# steering_wheel_V3_1.net
KiCad netlist of a schematic drawn in EAGLE
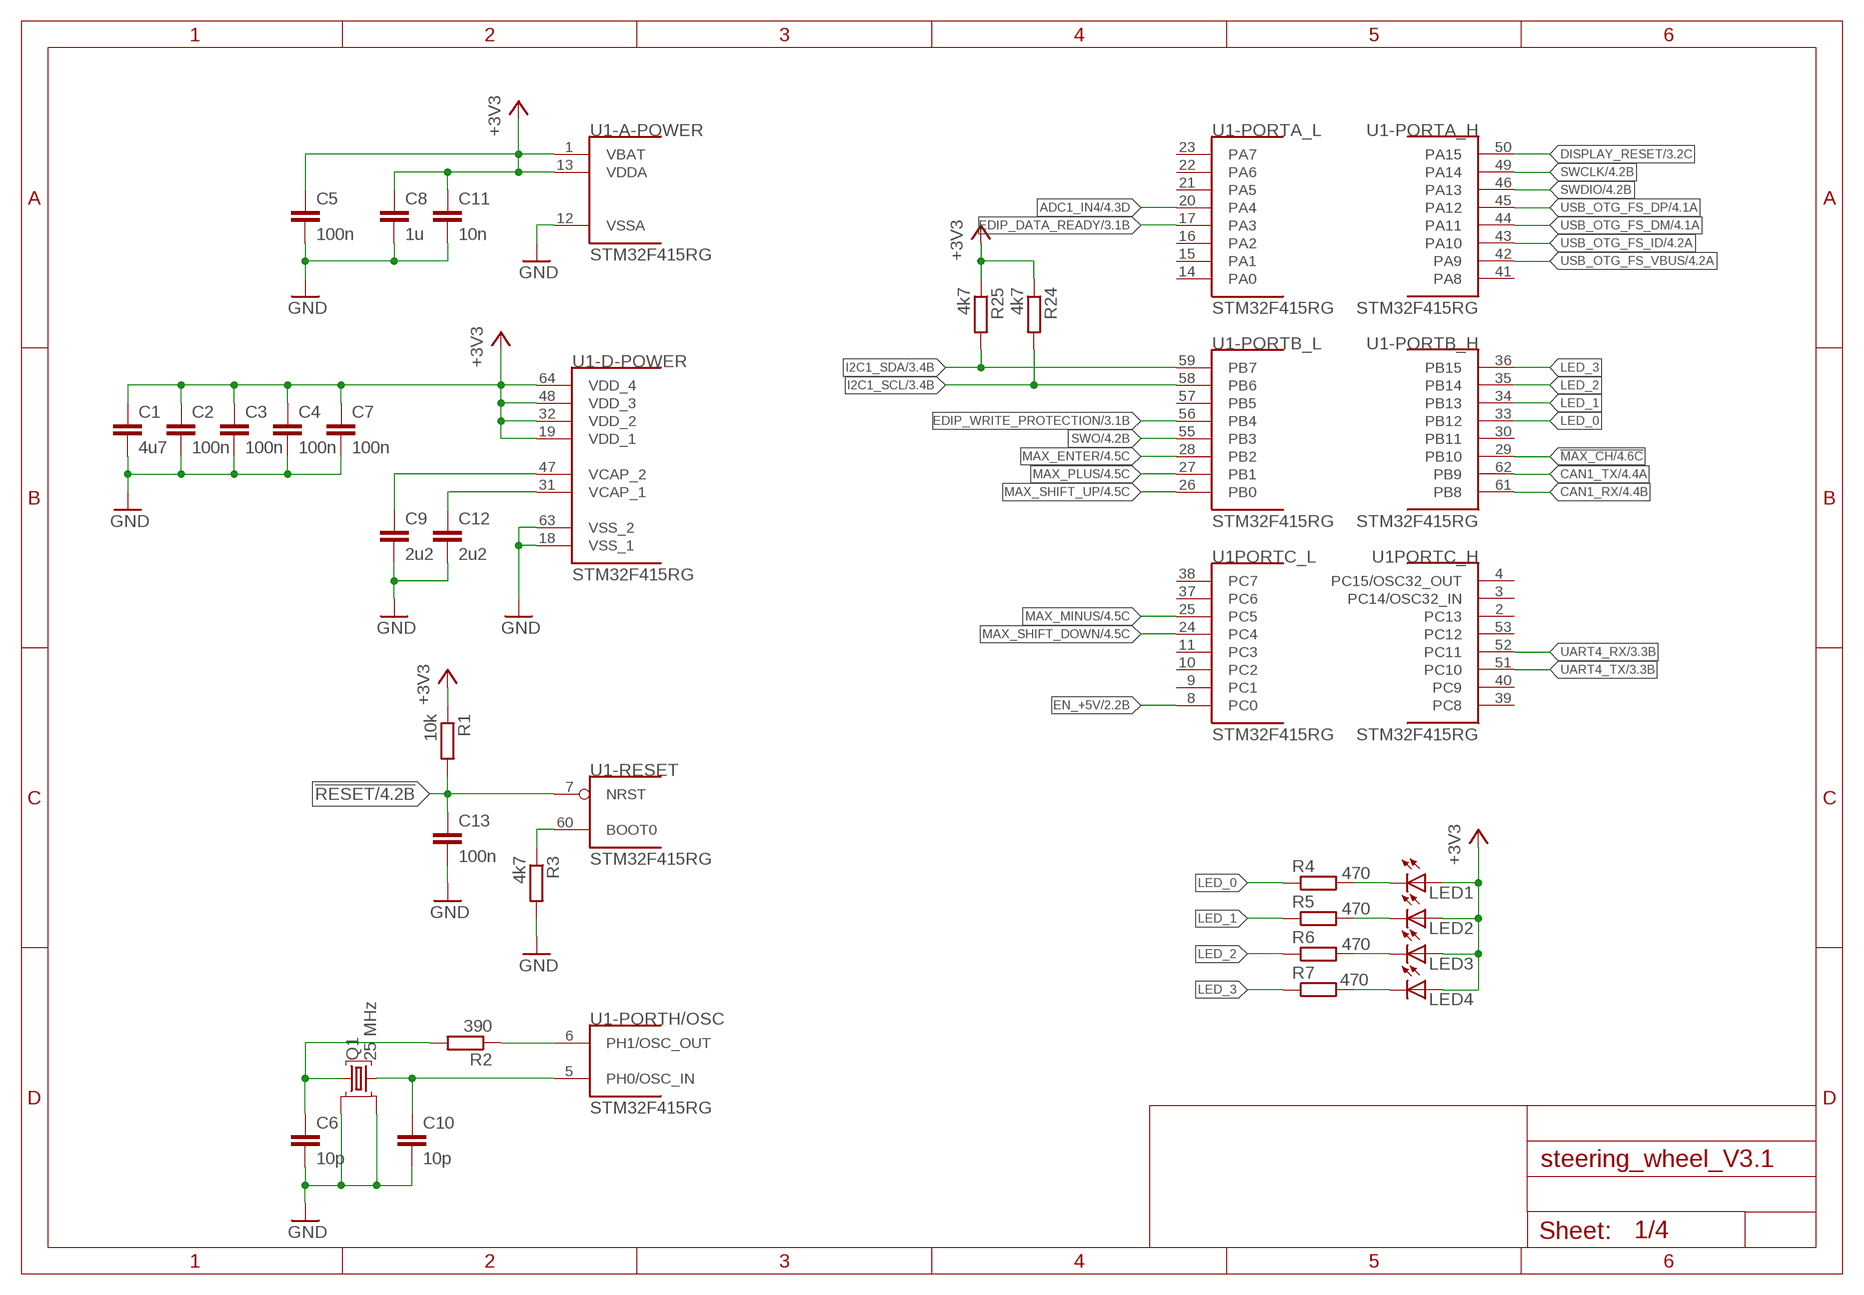
[diagram p0: schematic, sheet 1]
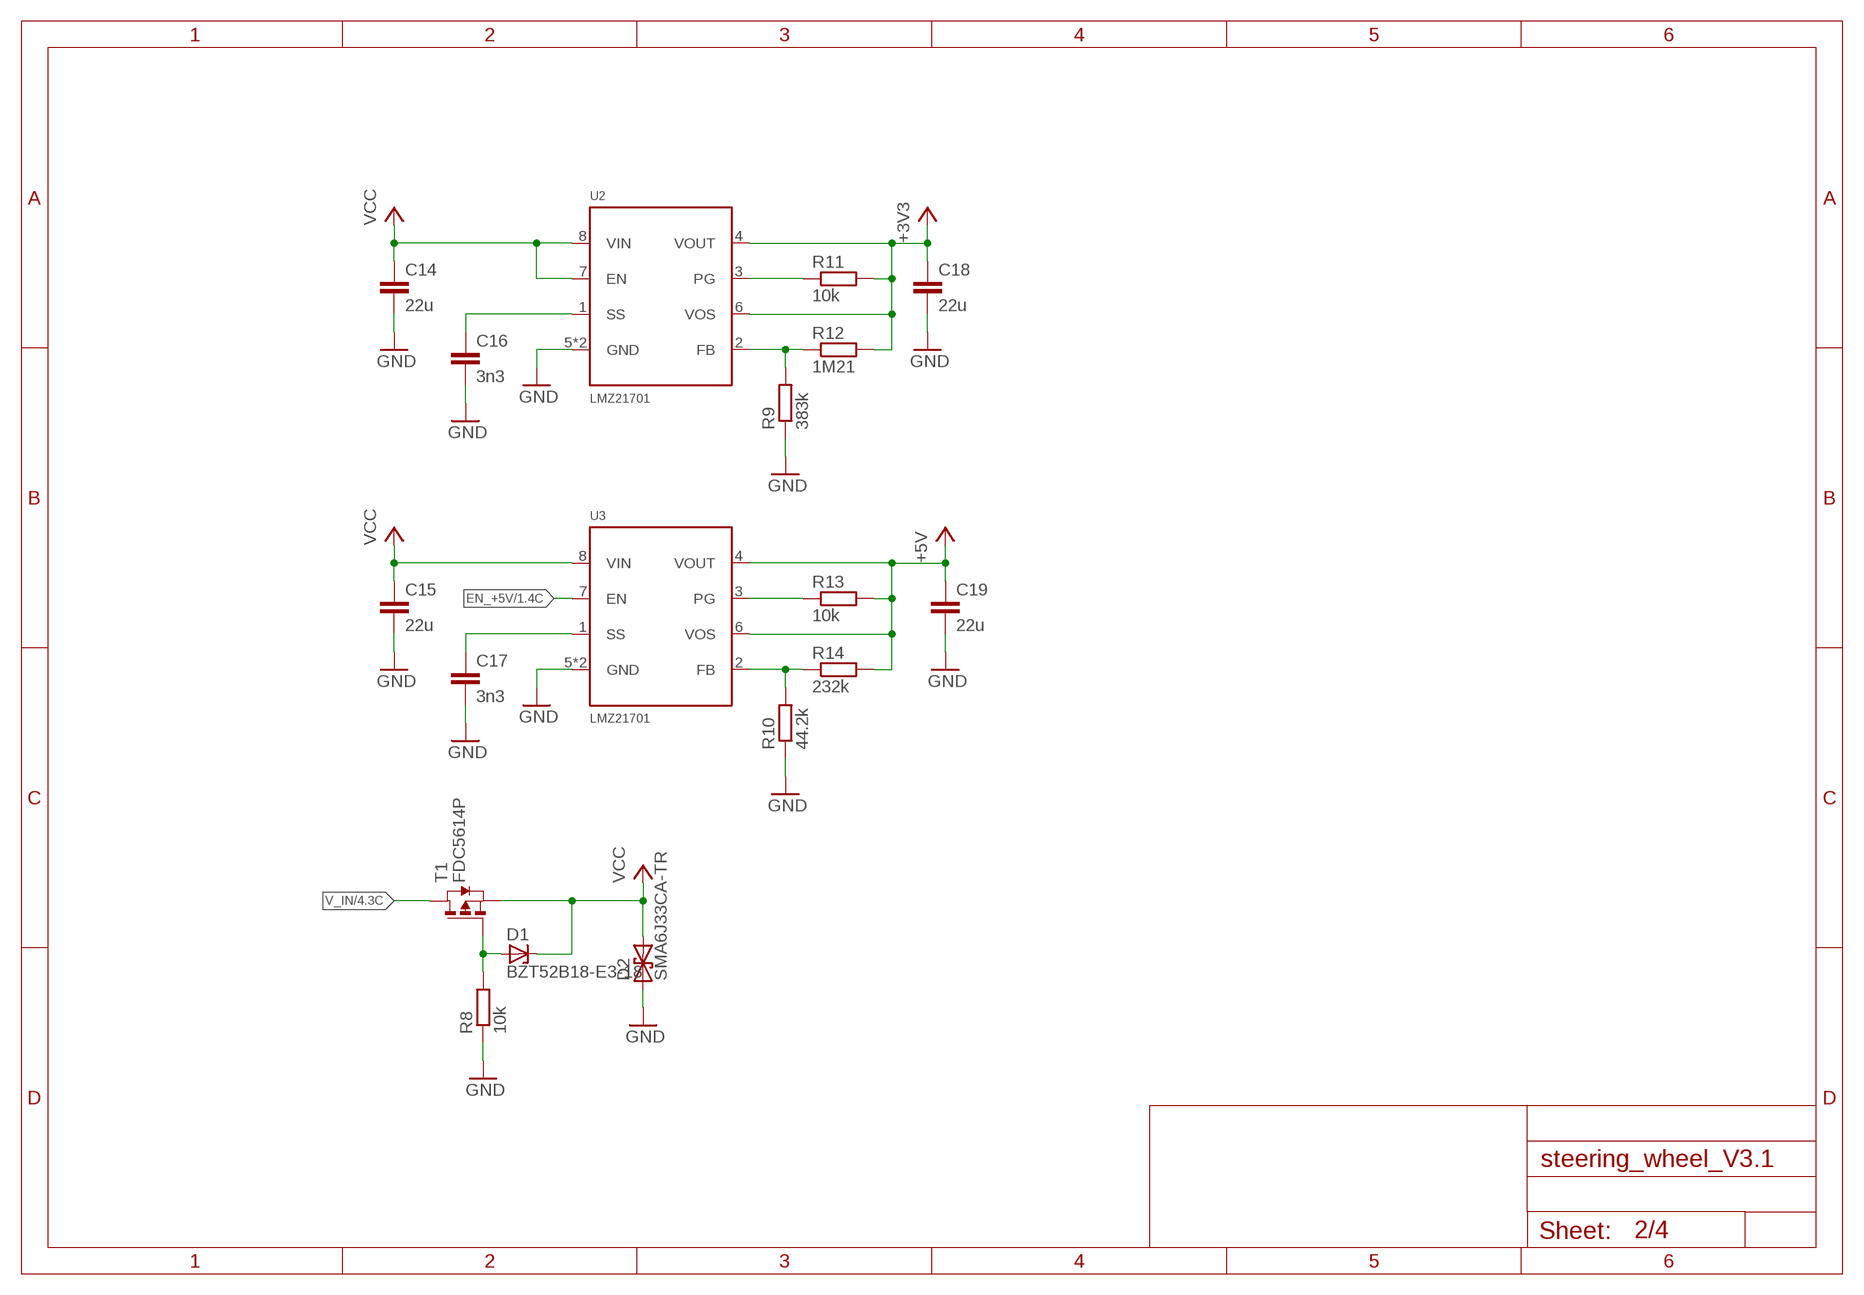
[diagram p1: schematic, sheet 2]
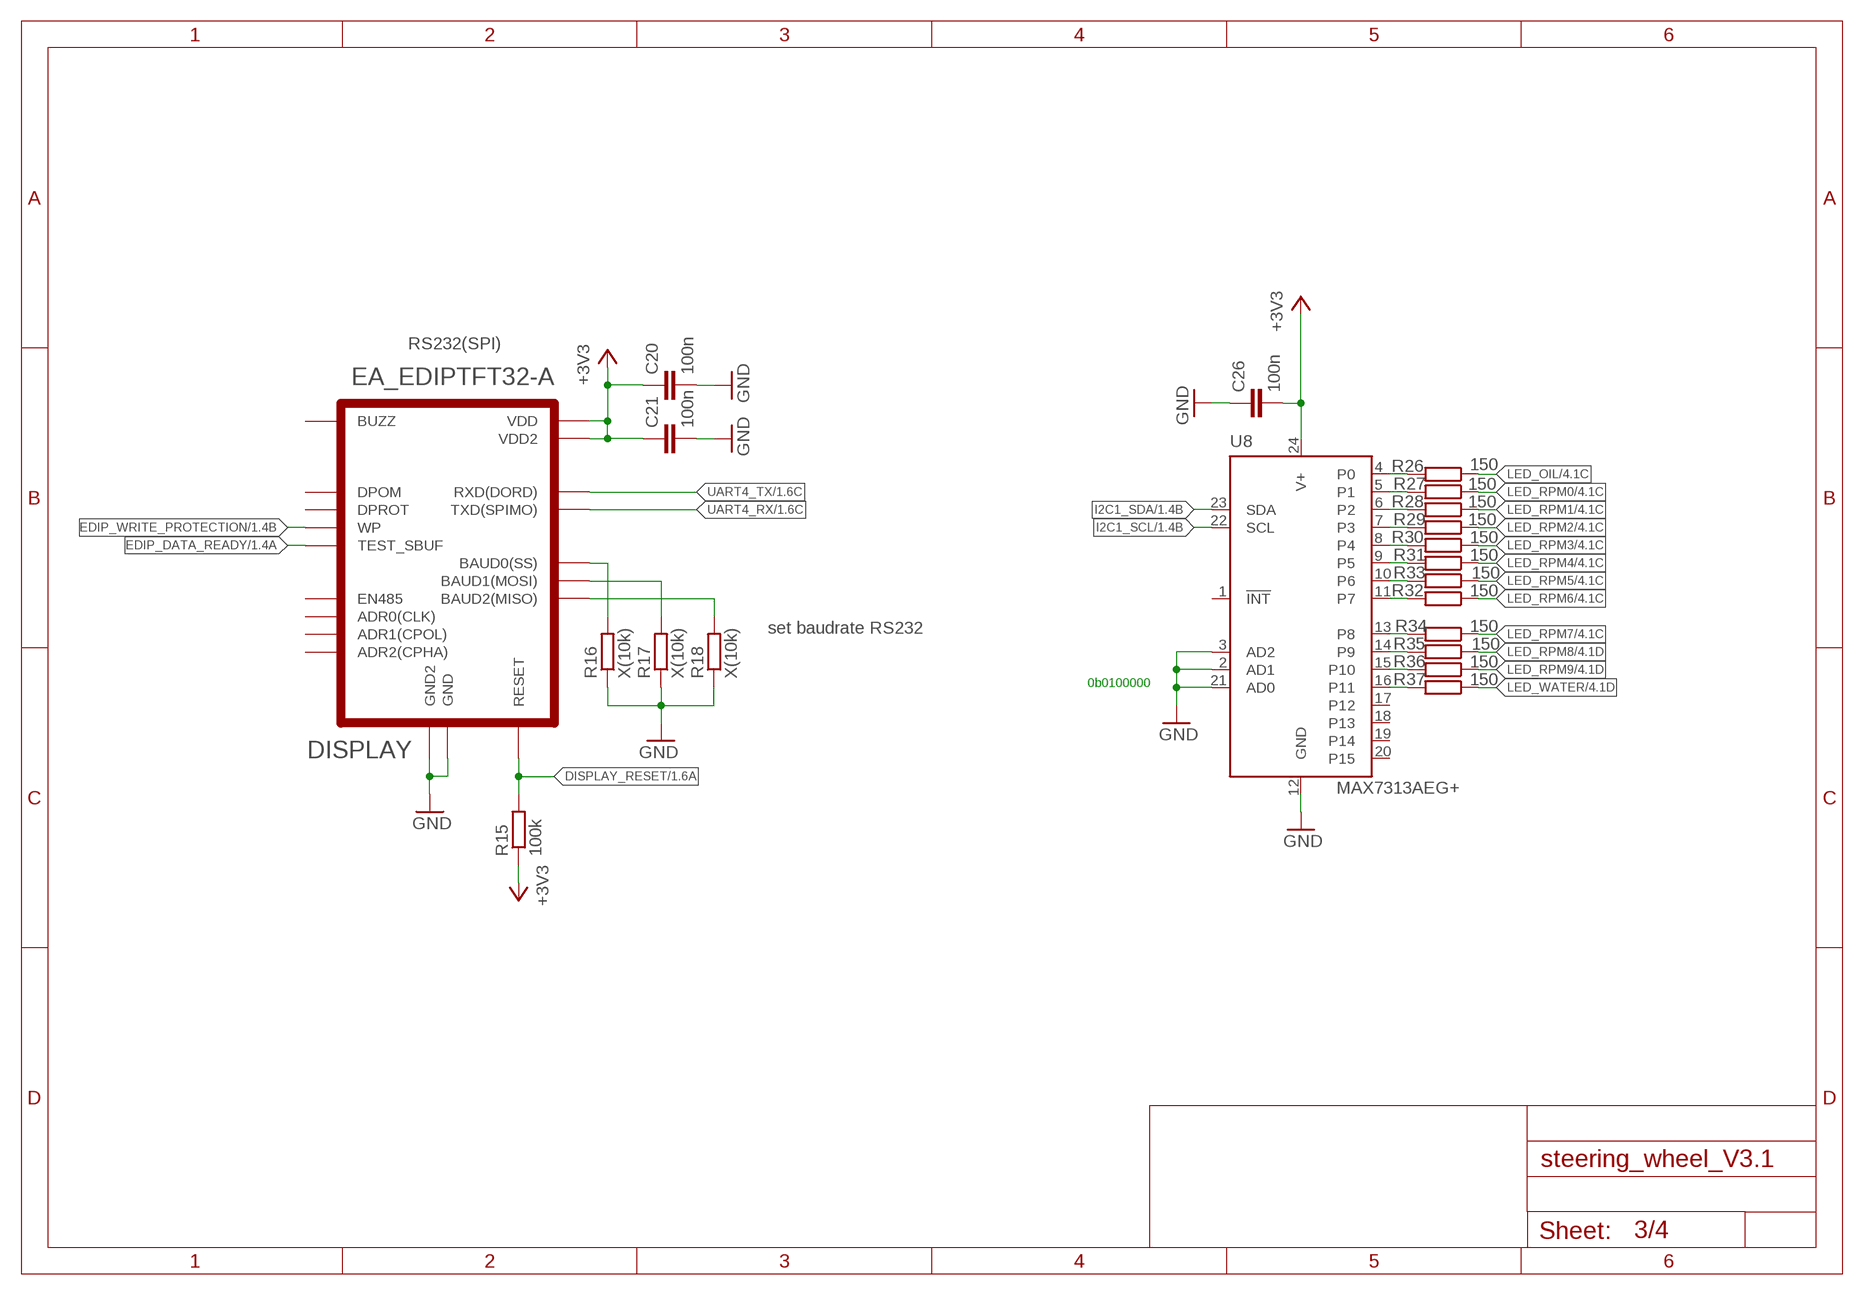
[diagram p2: schematic, sheet 3]
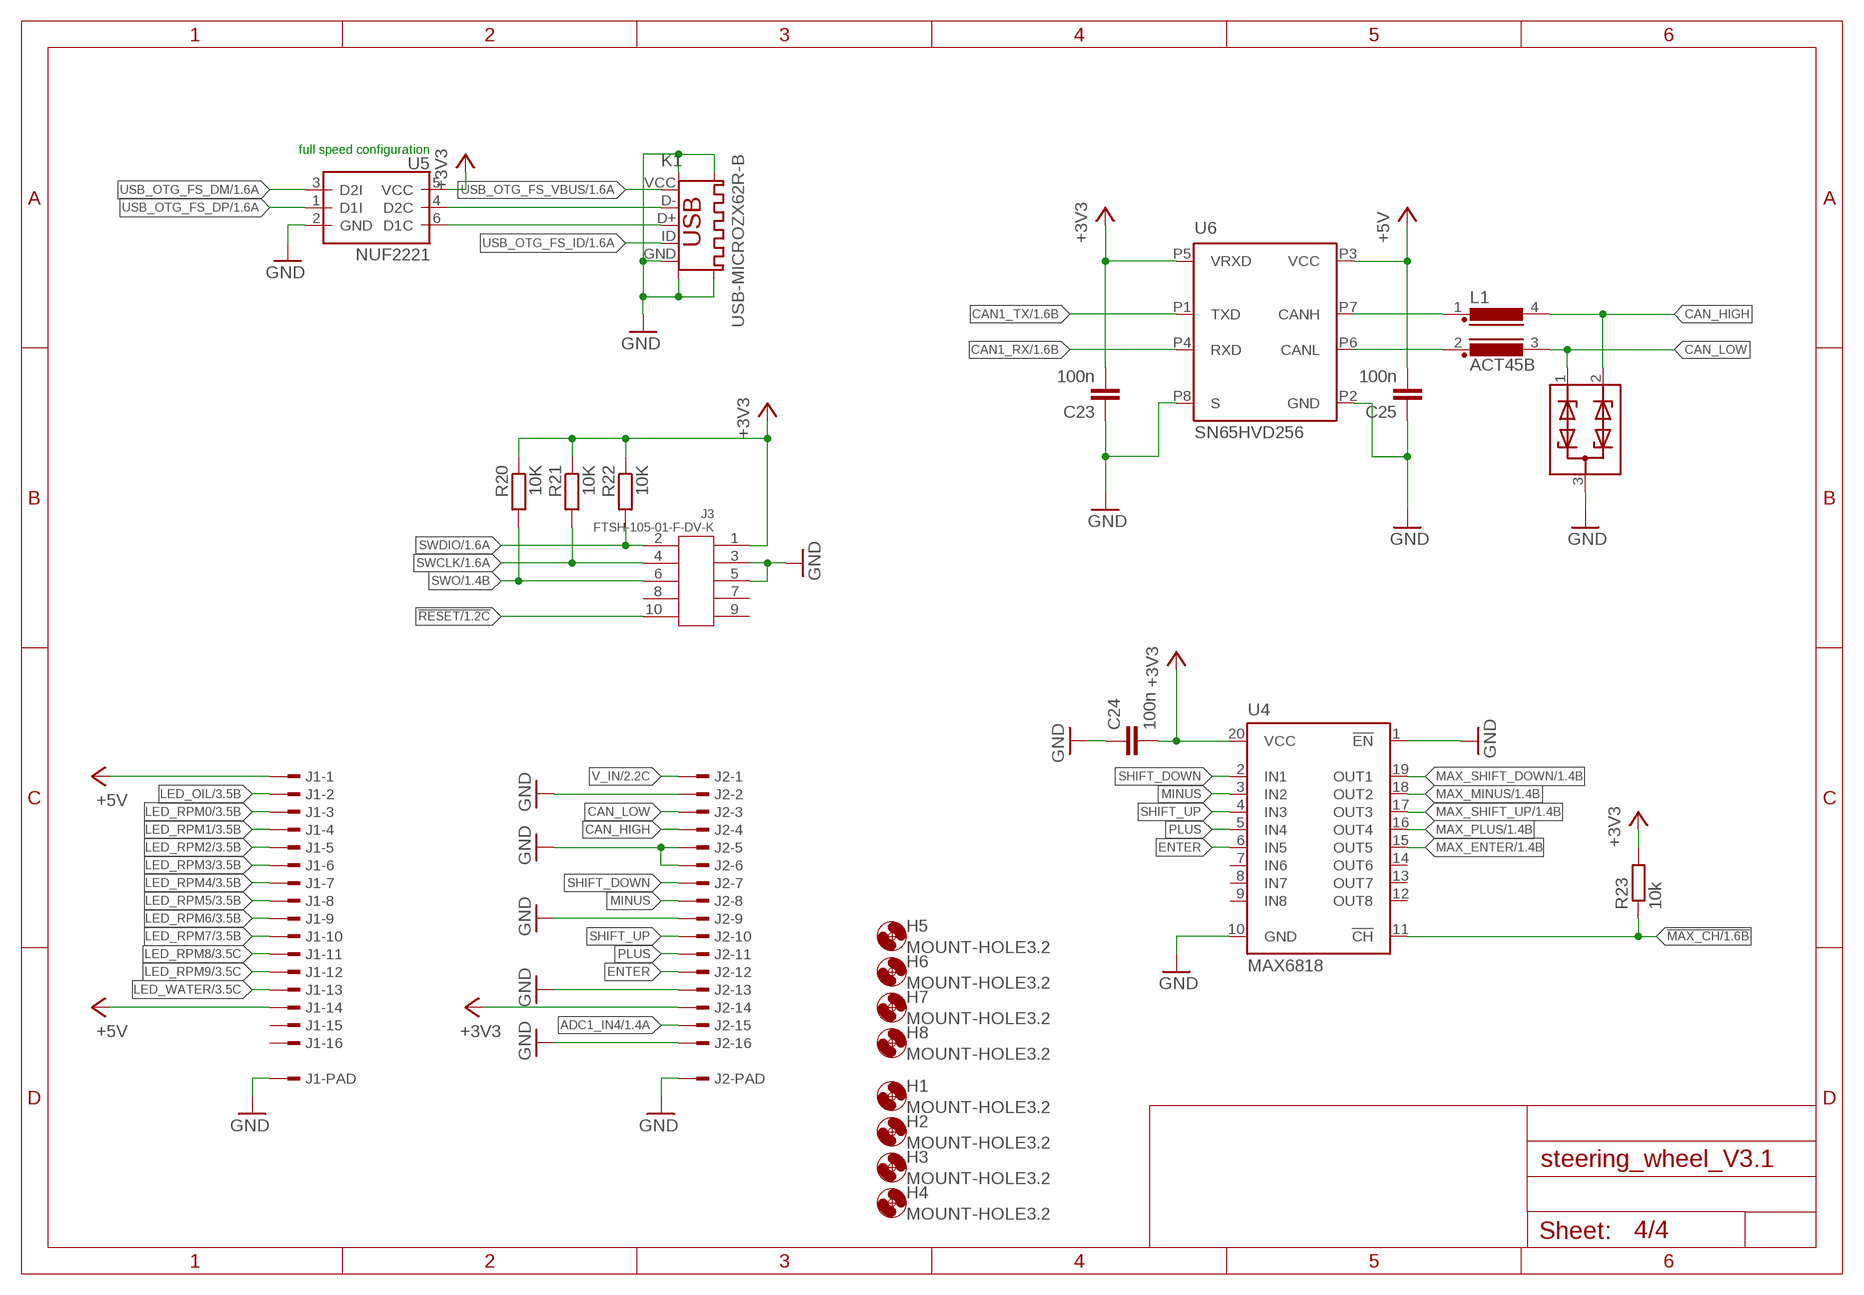
[diagram p3: schematic, sheet 4]

(export (version "E")
  (design (tool "Eeschema 10.0.6"))
  (components
    (comp (ref "C14")
      (value "22u")
      (footprint "eagle-import:C1210")
      (libsource (lib "eagle-import") (part "C-EUC1210"))
    )
    (comp (ref "C15")
      (value "22u")
      (footprint "eagle-import:C1210")
      (libsource (lib "eagle-import") (part "C-EUC1210"))
    )
    (comp (ref "C16")
      (value "3n3")
      (footprint "eagle-import:C0603")
      (libsource (lib "eagle-import") (part "C-EUC0603"))
    )
    (comp (ref "C17")
      (value "3n3")
      (footprint "eagle-import:C0603")
      (libsource (lib "eagle-import") (part "C-EUC0603"))
    )
    (comp (ref "C18")
      (value "22u")
      (footprint "eagle-import:C1210")
      (libsource (lib "eagle-import") (part "C-EUC1210"))
    )
    (comp (ref "C19")
      (value "22u")
      (footprint "eagle-import:C1210")
      (libsource (lib "eagle-import") (part "C-EUC1210"))
    )
    (comp (ref "D1")
      (value "BZT52B18-E3-18")
      (footprint "eagle-import:SOD123F")
      (libsource (lib "eagle-import") (part "ZENER_SOD123"))
    )
    (comp (ref "D2")
      (value "SMA6J33CA-TR")
      (footprint "eagle-import:DO214AC")
      (libsource (lib "eagle-import") (part "SMA6J33CA-TR"))
    )
    (comp (ref "R8")
      (value "10k")
      (footprint "eagle-import:R0603")
      (libsource (lib "eagle-import") (part "R-EU_R0603"))
    )
    (comp (ref "R9")
      (value "383k")
      (footprint "eagle-import:R0603")
      (libsource (lib "eagle-import") (part "R-EU_R0603"))
    )
    (comp (ref "R10")
      (value "44.2k")
      (footprint "eagle-import:R0603")
      (libsource (lib "eagle-import") (part "R-EU_R0603"))
    )
    (comp (ref "R11")
      (value "10k")
      (footprint "eagle-import:R0603")
      (libsource (lib "eagle-import") (part "R-EU_R0603"))
    )
    (comp (ref "R12")
      (value "1M21")
      (footprint "eagle-import:R0603")
      (libsource (lib "eagle-import") (part "R-EU_R0603"))
    )
    (comp (ref "R13")
      (value "10k")
      (footprint "eagle-import:R0603")
      (libsource (lib "eagle-import") (part "R-EU_R0603"))
    )
    (comp (ref "R14")
      (value "232k")
      (footprint "eagle-import:R0603")
      (libsource (lib "eagle-import") (part "R-EU_R0603"))
    )
    (comp (ref "T1")
      (value "FDC5614P")
      (footprint "eagle-import:SSOT6")
      (libsource (lib "eagle-import") (part "FDC5614P"))
    )
    (comp (ref "U2")
      (value "LMZ21701")
      (footprint "eagle-import:SIL0008E")
      (libsource (lib "eagle-import") (part "LMZ21701"))
    )
    (comp (ref "U3")
      (value "LMZ21701")
      (footprint "eagle-import:SIL0008E")
      (libsource (lib "eagle-import") (part "LMZ21701"))
    )
    (comp (ref "C20")
      (value "100n")
      (footprint "eagle-import:C0603")
      (libsource (lib "eagle-import") (part "C-EUC0603"))
    )
    (comp (ref "C21")
      (value "100n")
      (footprint "eagle-import:C0603")
      (libsource (lib "eagle-import") (part "C-EUC0603"))
    )
    (comp (ref "C26")
      (value "100n")
      (footprint "eagle-import:C0603")
      (libsource (lib "eagle-import") (part "C-EUC0603"))
    )
    (comp (ref "DISPLAY")
      (value "EA_EDIPTFT32-A")
      (footprint "eagle-import:EDIPTFT32-A")
      (libsource (lib "eagle-import") (part "EA_EDIPTFT32-A-SR232"))
    )
    (comp (ref "R15")
      (value "100k")
      (footprint "eagle-import:R0603")
      (libsource (lib "eagle-import") (part "R-EU_R0603"))
    )
    (comp (ref "R16")
      (value "X(10k)")
      (footprint "eagle-import:R0603")
      (libsource (lib "eagle-import") (part "R-EU_R0603"))
    )
    (comp (ref "R17")
      (value "X(10k)")
      (footprint "eagle-import:R0603")
      (libsource (lib "eagle-import") (part "R-EU_R0603"))
    )
    (comp (ref "R18")
      (value "X(10k)")
      (footprint "eagle-import:R0603")
      (libsource (lib "eagle-import") (part "R-EU_R0603"))
    )
    (comp (ref "R26")
      (value "150")
      (footprint "eagle-import:R0603")
      (libsource (lib "eagle-import") (part "R-EU_R0603"))
    )
    (comp (ref "R27")
      (value "150")
      (footprint "eagle-import:R0603")
      (libsource (lib "eagle-import") (part "R-EU_R0603"))
    )
    (comp (ref "R28")
      (value "150")
      (footprint "eagle-import:R0603")
      (libsource (lib "eagle-import") (part "R-EU_R0603"))
    )
    (comp (ref "R29")
      (value "150")
      (footprint "eagle-import:R0603")
      (libsource (lib "eagle-import") (part "R-EU_R0603"))
    )
    (comp (ref "R30")
      (value "150")
      (footprint "eagle-import:R0603")
      (libsource (lib "eagle-import") (part "R-EU_R0603"))
    )
    (comp (ref "R31")
      (value "150")
      (footprint "eagle-import:R0603")
      (libsource (lib "eagle-import") (part "R-EU_R0603"))
    )
    (comp (ref "R32")
      (value "150")
      (footprint "eagle-import:R0603")
      (libsource (lib "eagle-import") (part "R-EU_R0603"))
    )
    (comp (ref "R33")
      (value "150")
      (footprint "eagle-import:R0603")
      (libsource (lib "eagle-import") (part "R-EU_R0603"))
    )
    (comp (ref "R34")
      (value "150")
      (footprint "eagle-import:R0603")
      (libsource (lib "eagle-import") (part "R-EU_R0603"))
    )
    (comp (ref "R35")
      (value "150")
      (footprint "eagle-import:R0603")
      (libsource (lib "eagle-import") (part "R-EU_R0603"))
    )
    (comp (ref "R36")
      (value "150")
      (footprint "eagle-import:R0603")
      (libsource (lib "eagle-import") (part "R-EU_R0603"))
    )
    (comp (ref "R37")
      (value "150")
      (footprint "eagle-import:R0603")
      (libsource (lib "eagle-import") (part "R-EU_R0603"))
    )
    (comp (ref "U8")
      (value "MAX7313AEG+")
      (footprint "eagle-import:QSOP-24")
      (libsource (lib "eagle-import") (part "MAX7313AEG+"))
    )
    (comp (ref "C1")
      (value "4u7")
      (footprint "eagle-import:C0603")
      (libsource (lib "eagle-import") (part "C-EUC0603"))
    )
    (comp (ref "C2")
      (value "100n")
      (footprint "eagle-import:C0603")
      (libsource (lib "eagle-import") (part "C-EUC0603"))
    )
    (comp (ref "C3")
      (value "100n")
      (footprint "eagle-import:C0603")
      (libsource (lib "eagle-import") (part "C-EUC0603"))
    )
    (comp (ref "C4")
      (value "100n")
      (footprint "eagle-import:C0603")
      (libsource (lib "eagle-import") (part "C-EUC0603"))
    )
    (comp (ref "C5")
      (value "100n")
      (footprint "eagle-import:C0603")
      (libsource (lib "eagle-import") (part "C-EUC0603"))
    )
    (comp (ref "C6")
      (value "10p")
      (footprint "eagle-import:C0603")
      (libsource (lib "eagle-import") (part "C-EUC0603"))
    )
    (comp (ref "C7")
      (value "100n")
      (footprint "eagle-import:C0603")
      (libsource (lib "eagle-import") (part "C-EUC0603"))
    )
    (comp (ref "C8")
      (value "1u")
      (footprint "eagle-import:C0603")
      (libsource (lib "eagle-import") (part "C-EUC0603"))
    )
    (comp (ref "C9")
      (value "2u2")
      (footprint "eagle-import:C0603")
      (libsource (lib "eagle-import") (part "C-EUC0603"))
    )
    (comp (ref "C10")
      (value "10p")
      (footprint "eagle-import:C0603")
      (libsource (lib "eagle-import") (part "C-EUC0603"))
    )
    (comp (ref "C11")
      (value "10n")
      (footprint "eagle-import:C0603")
      (libsource (lib "eagle-import") (part "C-EUC0603"))
    )
    (comp (ref "C12")
      (value "2u2")
      (footprint "eagle-import:C0603")
      (libsource (lib "eagle-import") (part "C-EUC0603"))
    )
    (comp (ref "C13")
      (value "100n")
      (footprint "eagle-import:C0603")
      (libsource (lib "eagle-import") (part "C-EUC0603"))
    )
    (comp (ref "LED1")
      (value "LEDCHIPLED_0603")
      (footprint "eagle-import:CHIPLED_0603")
      (libsource (lib "eagle-import") (part "LEDCHIPLED_0603"))
    )
    (comp (ref "LED2")
      (value "LEDCHIPLED_0603")
      (footprint "eagle-import:CHIPLED_0603")
      (libsource (lib "eagle-import") (part "LEDCHIPLED_0603"))
    )
    (comp (ref "LED3")
      (value "LEDCHIPLED_0603")
      (footprint "eagle-import:CHIPLED_0603")
      (libsource (lib "eagle-import") (part "LEDCHIPLED_0603"))
    )
    (comp (ref "LED4")
      (value "LEDCHIPLED_0603")
      (footprint "eagle-import:CHIPLED_0603")
      (libsource (lib "eagle-import") (part "LEDCHIPLED_0603"))
    )
    (comp (ref "Q1")
      (value "25 MHz")
      (footprint "eagle-import:3.2X2.5MM-SMD")
      (libsource (lib "eagle-import") (part "CRYSTAL2M_CX32"))
    )
    (comp (ref "R1")
      (value "10k")
      (footprint "eagle-import:R0603")
      (libsource (lib "eagle-import") (part "R-EU_R0603"))
    )
    (comp (ref "R2")
      (value "390")
      (footprint "eagle-import:R0603")
      (libsource (lib "eagle-import") (part "R-EU_R0603"))
    )
    (comp (ref "R3")
      (value "4k7")
      (footprint "eagle-import:R0603")
      (libsource (lib "eagle-import") (part "R-EU_R0603"))
    )
    (comp (ref "R4")
      (value "470")
      (footprint "eagle-import:R0603")
      (libsource (lib "eagle-import") (part "R-EU_R0603"))
    )
    (comp (ref "R5")
      (value "470")
      (footprint "eagle-import:R0603")
      (libsource (lib "eagle-import") (part "R-EU_R0603"))
    )
    (comp (ref "R6")
      (value "470")
      (footprint "eagle-import:R0603")
      (libsource (lib "eagle-import") (part "R-EU_R0603"))
    )
    (comp (ref "R7")
      (value "470")
      (footprint "eagle-import:R0603")
      (libsource (lib "eagle-import") (part "R-EU_R0603"))
    )
    (comp (ref "R24")
      (value "4k7")
      (footprint "eagle-import:R0603")
      (libsource (lib "eagle-import") (part "R-EU_R0603"))
    )
    (comp (ref "R25")
      (value "4k7")
      (footprint "eagle-import:R0603")
      (libsource (lib "eagle-import") (part "R-EU_R0603"))
    )
    (comp (ref "U1")
      (value "STM32F415RG")
      (footprint "eagle-import:LQFP64")
      (libsource (lib "eagle-import") (part "STM32F415RG"))
    )
    (comp (ref "C23")
      (value "100n")
      (footprint "eagle-import:C0603")
      (libsource (lib "eagle-import") (part "C-EUC0603"))
    )
    (comp (ref "C24")
      (value "100n")
      (footprint "eagle-import:C0603")
      (libsource (lib "eagle-import") (part "C-EUC0603"))
    )
    (comp (ref "C25")
      (value "100n")
      (footprint "eagle-import:C0603")
      (libsource (lib "eagle-import") (part "C-EUC0603"))
    )
    (comp (ref "D3")
      (value "PESD1CAN-U")
      (footprint "eagle-import:SOT-323")
      (libsource (lib "eagle-import") (part "PESD1CAN-U"))
    )
    (comp (ref "H1")
      (value "MOUNT-HOLE3.2")
      (footprint "eagle-import:3,2")
      (libsource (lib "eagle-import") (part "MOUNT-HOLE3.2"))
    )
    (comp (ref "H2")
      (value "MOUNT-HOLE3.2")
      (footprint "eagle-import:3,2")
      (libsource (lib "eagle-import") (part "MOUNT-HOLE3.2"))
    )
    (comp (ref "H3")
      (value "MOUNT-HOLE3.2")
      (footprint "eagle-import:3,2")
      (libsource (lib "eagle-import") (part "MOUNT-HOLE3.2"))
    )
    (comp (ref "H4")
      (value "MOUNT-HOLE3.2")
      (footprint "eagle-import:3,2")
      (libsource (lib "eagle-import") (part "MOUNT-HOLE3.2"))
    )
    (comp (ref "H5")
      (value "MOUNT-HOLE3.2")
      (footprint "eagle-import:3,2")
      (libsource (lib "eagle-import") (part "MOUNT-HOLE3.2"))
    )
    (comp (ref "H6")
      (value "MOUNT-HOLE3.2")
      (footprint "eagle-import:3,2")
      (libsource (lib "eagle-import") (part "MOUNT-HOLE3.2"))
    )
    (comp (ref "H7")
      (value "MOUNT-HOLE3.2")
      (footprint "eagle-import:3,2")
      (libsource (lib "eagle-import") (part "MOUNT-HOLE3.2"))
    )
    (comp (ref "H8")
      (value "MOUNT-HOLE3.2")
      (footprint "eagle-import:3,2")
      (libsource (lib "eagle-import") (part "MOUNT-HOLE3.2"))
    )
    (comp (ref "J1")
      (value "1-292227-6")
      (footprint "eagle-import:1-292227-6")
      (libsource (lib "eagle-import") (part "1-292227-6"))
    )
    (comp (ref "J2")
      (value "1-292227-6")
      (footprint "eagle-import:1-292227-6")
      (libsource (lib "eagle-import") (part "1-292227-6"))
    )
    (comp (ref "J3")
      (value "FTSH-105-01-F-DV-K")
      (footprint "eagle-import:FTSH-105-01-XXX-DV-K")
      (libsource (lib "eagle-import") (part "FTSH-105-01--DV-KF"))
    )
    (comp (ref "K1")
      (value "USB-MICROZX62R-B")
      (footprint "eagle-import:ZX62R-B")
      (libsource (lib "eagle-import") (part "USB-MICROZX62R-B"))
    )
    (comp (ref "L1")
      (value "ACT45B")
      (footprint "eagle-import:ACT45B")
      (libsource (lib "eagle-import") (part "ACT45B"))
    )
    (comp (ref "R20")
      (value "10K")
      (footprint "eagle-import:R0603")
      (libsource (lib "eagle-import") (part "R-EU_R0603"))
    )
    (comp (ref "R21")
      (value "10K")
      (footprint "eagle-import:R0603")
      (libsource (lib "eagle-import") (part "R-EU_R0603"))
    )
    (comp (ref "R22")
      (value "10K")
      (footprint "eagle-import:R0603")
      (libsource (lib "eagle-import") (part "R-EU_R0603"))
    )
    (comp (ref "R23")
      (value "10k")
      (footprint "eagle-import:R0603")
      (libsource (lib "eagle-import") (part "R-EU_R0603"))
    )
    (comp (ref "U4")
      (value "MAX6818")
      (footprint "eagle-import:SSOP-20")
      (libsource (lib "eagle-import") (part "MAX6818"))
    )
    (comp (ref "U5")
      (value "NUF2221")
      (footprint "eagle-import:SOT363")
      (fields
        (field (name "OC_DIGIKEY") "NUF2221W1T2GOSCT-ND")
        (field (name "ORDER_CODE") "NUF2221W1T2GOSCT-ND")
      )
      (libsource (lib "eagle-import") (part "NUF2221"))
    )
    (comp (ref "U6")
      (value "SN65HVD256")
      (footprint "eagle-import:SOIC8")
      (libsource (lib "eagle-import") (part "SN65HVD256"))
    )
  )
  (nets
    (net (code "1") (name "+3V3") (class "Default")
      (node (ref "C1") (pin "1") (pinfunction "1_1") (pintype "passive"))
      (node (ref "C11") (pin "1") (pinfunction "1_1") (pintype "passive"))
      (node (ref "C18") (pin "1") (pinfunction "1_1") (pintype "passive"))
      (node (ref "C2") (pin "1") (pinfunction "1_1") (pintype "passive"))
      (node (ref "C20") (pin "1") (pinfunction "1_1") (pintype "passive"))
      (node (ref "C21") (pin "1") (pinfunction "1_1") (pintype "passive"))
      (node (ref "C23") (pin "2") (pinfunction "2_2") (pintype "passive"))
      (node (ref "C24") (pin "2") (pinfunction "2_2") (pintype "passive"))
      (node (ref "C26") (pin "2") (pinfunction "2_2") (pintype "passive"))
      (node (ref "C3") (pin "1") (pinfunction "1_1") (pintype "passive"))
      (node (ref "C4") (pin "1") (pinfunction "1_1") (pintype "passive"))
      (node (ref "C5") (pin "1") (pinfunction "1_1") (pintype "passive"))
      (node (ref "C7") (pin "1") (pinfunction "1_1") (pintype "passive"))
      (node (ref "C8") (pin "1") (pinfunction "1_1") (pintype "passive"))
      (node (ref "DISPLAY") (pin "P$2") (pinfunction "VDD_P$2") (pintype "bidirectional"))
      (node (ref "DISPLAY") (pin "P$22") (pinfunction "VDD2_P$22") (pintype "bidirectional"))
      (node (ref "J2") (pin "14") (pinfunction "1_14") (pintype "passive"))
      (node (ref "J3") (pin "1") (pinfunction "1_1") (pintype "passive"))
      (node (ref "LED1") (pin "A") (pinfunction "A_A") (pintype "passive"))
      (node (ref "LED2") (pin "A") (pinfunction "A_A") (pintype "passive"))
      (node (ref "LED3") (pin "A") (pinfunction "A_A") (pintype "passive"))
      (node (ref "LED4") (pin "A") (pinfunction "A_A") (pintype "passive"))
      (node (ref "R1") (pin "1") (pinfunction "1_1") (pintype "passive"))
      (node (ref "R11") (pin "2") (pinfunction "2_2") (pintype "passive"))
      (node (ref "R12") (pin "2") (pinfunction "2_2") (pintype "passive"))
      (node (ref "R15") (pin "1") (pinfunction "1_1") (pintype "passive"))
      (node (ref "R20") (pin "1") (pinfunction "1_1") (pintype "passive"))
      (node (ref "R21") (pin "1") (pinfunction "1_1") (pintype "passive"))
      (node (ref "R22") (pin "1") (pinfunction "1_1") (pintype "passive"))
      (node (ref "R23") (pin "2") (pinfunction "2_2") (pintype "passive"))
      (node (ref "R24") (pin "1") (pinfunction "1_1") (pintype "passive"))
      (node (ref "R25") (pin "1") (pinfunction "1_1") (pintype "passive"))
      (node (ref "U1") (pin "1") (pinfunction "VBAT_1") (pintype "power_in"))
      (node (ref "U1") (pin "13") (pinfunction "VDDA_13") (pintype "power_in"))
      (node (ref "U1") (pin "19") (pinfunction "VDD_1_19") (pintype "power_in"))
      (node (ref "U1") (pin "32") (pinfunction "VDD_2_32") (pintype "power_in"))
      (node (ref "U1") (pin "48") (pinfunction "VDD_3_48") (pintype "power_in"))
      (node (ref "U1") (pin "64") (pinfunction "VDD_4_64") (pintype "power_in"))
      (node (ref "U2") (pin "4") (pinfunction "VOUT_4") (pintype "passive"))
      (node (ref "U2") (pin "6") (pinfunction "VOS_6") (pintype "input"))
      (node (ref "U4") (pin "20") (pinfunction "VCC_20") (pintype "bidirectional"))
      (node (ref "U5") (pin "5") (pinfunction "VCC_5") (pintype "power_in"))
      (node (ref "U6") (pin "P5") (pinfunction "VRXD_P5") (pintype "power_in"))
      (node (ref "U8") (pin "24") (pinfunction "V+_24") (pintype "power_in"))
    )
    (net (code "2") (name "+5V") (class "Default")
      (node (ref "C19") (pin "1") (pinfunction "1_1") (pintype "passive"))
      (node (ref "C25") (pin "2") (pinfunction "2_2") (pintype "passive"))
      (node (ref "J1") (pin "1") (pinfunction "1_1") (pintype "passive"))
      (node (ref "J1") (pin "14") (pinfunction "1_14") (pintype "passive"))
      (node (ref "R13") (pin "2") (pinfunction "2_2") (pintype "passive"))
      (node (ref "R14") (pin "2") (pinfunction "2_2") (pintype "passive"))
      (node (ref "U3") (pin "4") (pinfunction "VOUT_4") (pintype "passive"))
      (node (ref "U3") (pin "6") (pinfunction "VOS_6") (pintype "input"))
      (node (ref "U6") (pin "P3") (pinfunction "VCC_P3") (pintype "power_in"))
    )
    (net (code "3") (name "ADC1_IN4") (class "Default")
      (node (ref "J2") (pin "15") (pinfunction "1_15") (pintype "passive"))
      (node (ref "U1") (pin "20") (pinfunction "PA4_20") (pintype "bidirectional"))
    )
    (net (code "4") (name "CAN1_RX") (class "Default")
      (node (ref "U1") (pin "61") (pinfunction "PB8_61") (pintype "bidirectional"))
      (node (ref "U6") (pin "P4") (pinfunction "RXD_P4") (pintype "output"))
    )
    (net (code "5") (name "CAN1_TX") (class "Default")
      (node (ref "U1") (pin "62") (pinfunction "PB9_62") (pintype "bidirectional"))
      (node (ref "U6") (pin "P1") (pinfunction "TXD_P1") (pintype "input"))
    )
    (net (code "6") (name "CAN_HIGH") (class "Default")
      (node (ref "D3") (pin "2") (pinfunction "2_2") (pintype "passive"))
      (node (ref "J2") (pin "4") (pinfunction "1_4") (pintype "passive"))
      (node (ref "L1") (pin "4") (pinfunction "4_4") (pintype "passive"))
    )
    (net (code "7") (name "CAN_LOW") (class "Default")
      (node (ref "D3") (pin "1") (pinfunction "1_1") (pintype "passive"))
      (node (ref "J2") (pin "3") (pinfunction "1_3") (pintype "passive"))
      (node (ref "L1") (pin "3") (pinfunction "3_3") (pintype "passive"))
    )
    (net (code "8") (name "DISPLAY_RESET") (class "Default")
      (node (ref "DISPLAY") (pin "P$5") (pinfunction "RESET_P$5") (pintype "bidirectional"))
      (node (ref "R15") (pin "2") (pinfunction "2_2") (pintype "passive"))
      (node (ref "U1") (pin "50") (pinfunction "PA15_50") (pintype "bidirectional"))
    )
    (net (code "9") (name "EDIP_DATA_READY") (class "Default")
      (node (ref "DISPLAY") (pin "P$20") (pinfunction "TEST_SBUF_P$20") (pintype "bidirectional"))
      (node (ref "U1") (pin "17") (pinfunction "PA3_17") (pintype "bidirectional"))
    )
    (net (code "10") (name "EDIP_WRITE_PROTECTION") (class "Default")
      (node (ref "DISPLAY") (pin "P$19") (pinfunction "WP_P$19") (pintype "bidirectional"))
      (node (ref "U1") (pin "56") (pinfunction "PB4_56") (pintype "bidirectional"))
    )
    (net (code "11") (name "ENTER") (class "Default")
      (node (ref "J2") (pin "12") (pinfunction "1_12") (pintype "passive"))
      (node (ref "U4") (pin "6") (pinfunction "IN5_6") (pintype "bidirectional"))
    )
    (net (code "12") (name "EN_+5V") (class "Default")
      (node (ref "U1") (pin "8") (pinfunction "PC0_8") (pintype "bidirectional"))
      (node (ref "U3") (pin "7") (pinfunction "EN_7") (pintype "input"))
    )
    (net (code "13") (name "GND") (class "Default")
      (node (ref "C1") (pin "2") (pinfunction "2_2") (pintype "passive"))
      (node (ref "C10") (pin "2") (pinfunction "2_2") (pintype "passive"))
      (node (ref "C11") (pin "2") (pinfunction "2_2") (pintype "passive"))
      (node (ref "C12") (pin "2") (pinfunction "2_2") (pintype "passive"))
      (node (ref "C13") (pin "2") (pinfunction "2_2") (pintype "passive"))
      (node (ref "C14") (pin "2") (pinfunction "2_2") (pintype "passive"))
      (node (ref "C15") (pin "2") (pinfunction "2_2") (pintype "passive"))
      (node (ref "C16") (pin "2") (pinfunction "2_2") (pintype "passive"))
      (node (ref "C17") (pin "2") (pinfunction "2_2") (pintype "passive"))
      (node (ref "C18") (pin "2") (pinfunction "2_2") (pintype "passive"))
      (node (ref "C19") (pin "2") (pinfunction "2_2") (pintype "passive"))
      (node (ref "C2") (pin "2") (pinfunction "2_2") (pintype "passive"))
      (node (ref "C20") (pin "2") (pinfunction "2_2") (pintype "passive"))
      (node (ref "C21") (pin "2") (pinfunction "2_2") (pintype "passive"))
      (node (ref "C23") (pin "1") (pinfunction "1_1") (pintype "passive"))
      (node (ref "C24") (pin "1") (pinfunction "1_1") (pintype "passive"))
      (node (ref "C25") (pin "1") (pinfunction "1_1") (pintype "passive"))
      (node (ref "C26") (pin "1") (pinfunction "1_1") (pintype "passive"))
      (node (ref "C3") (pin "2") (pinfunction "2_2") (pintype "passive"))
      (node (ref "C4") (pin "2") (pinfunction "2_2") (pintype "passive"))
      (node (ref "C5") (pin "2") (pinfunction "2_2") (pintype "passive"))
      (node (ref "C6") (pin "2") (pinfunction "2_2") (pintype "passive"))
      (node (ref "C7") (pin "2") (pinfunction "2_2") (pintype "passive"))
      (node (ref "C8") (pin "2") (pinfunction "2_2") (pintype "passive"))
      (node (ref "C9") (pin "2") (pinfunction "2_2") (pintype "passive"))
      (node (ref "D2") (pin "A") (pinfunction "1_A") (pintype "passive"))
      (node (ref "D3") (pin "3") (pinfunction "3_3") (pintype "passive"))
      (node (ref "DISPLAY") (pin "P$1") (pinfunction "GND_P$1") (pintype "bidirectional"))
      (node (ref "DISPLAY") (pin "P$21") (pinfunction "GND2_P$21") (pintype "bidirectional"))
      (node (ref "J1") (pin "PAD1") (pinfunction "1_PAD1") (pintype "passive"))
      (node (ref "J1") (pin "PAD2") (pinfunction "1_PAD2") (pintype "passive"))
      (node (ref "J2") (pin "13") (pinfunction "1_13") (pintype "passive"))
      (node (ref "J2") (pin "16") (pinfunction "1_16") (pintype "passive"))
      (node (ref "J2") (pin "2") (pinfunction "1_2") (pintype "passive"))
      (node (ref "J2") (pin "5") (pinfunction "1_5") (pintype "passive"))
      (node (ref "J2") (pin "6") (pinfunction "1_6") (pintype "passive"))
      (node (ref "J2") (pin "9") (pinfunction "1_9") (pintype "passive"))
      (node (ref "J2") (pin "PAD1") (pinfunction "1_PAD1") (pintype "passive"))
      (node (ref "J2") (pin "PAD2") (pinfunction "1_PAD2") (pintype "passive"))
      (node (ref "J3") (pin "3") (pinfunction "3_3") (pintype "passive"))
      (node (ref "J3") (pin "5") (pinfunction "5_5") (pintype "passive"))
      (node (ref "K1") (pin "GND") (pinfunction "GND_GND") (pintype "passive"))
      (node (ref "K1") (pin "P$6") (pinfunction "GND3_P$6") (pintype "bidirectional"))
      (node (ref "K1") (pin "P$7") (pinfunction "GND4_P$7") (pintype "bidirectional"))
      (node (ref "K1") (pin "P$8") (pinfunction "GND1_P$8") (pintype "bidirectional"))
      (node (ref "K1") (pin "P$9") (pinfunction "GND2_P$9") (pintype "bidirectional"))
      (node (ref "Q1") (pin "2") (pinfunction "GND1_2") (pintype "power_in"))
      (node (ref "Q1") (pin "4") (pinfunction "GND2_4") (pintype "power_in"))
      (node (ref "R10") (pin "1") (pinfunction "1_1") (pintype "passive"))
      (node (ref "R16") (pin "1") (pinfunction "1_1") (pintype "passive"))
      (node (ref "R17") (pin "1") (pinfunction "1_1") (pintype "passive"))
      (node (ref "R18") (pin "1") (pinfunction "1_1") (pintype "passive"))
      (node (ref "R3") (pin "2") (pinfunction "2_2") (pintype "passive"))
      (node (ref "R8") (pin "1") (pinfunction "1_1") (pintype "passive"))
      (node (ref "R9") (pin "1") (pinfunction "1_1") (pintype "passive"))
      (node (ref "U1") (pin "12") (pinfunction "VSSA_12") (pintype "power_in"))
      (node (ref "U1") (pin "18") (pinfunction "VSS_1_18") (pintype "power_in"))
      (node (ref "U1") (pin "63") (pinfunction "VSS_2_63") (pintype "power_in"))
      (node (ref "U2") (pin "5") (pinfunction "GND_5") (pintype "power_in"))
      (node (ref "U2") (pin "PAD") (pinfunction "GND_PAD") (pintype "power_in"))
      (node (ref "U3") (pin "5") (pinfunction "GND_5") (pintype "power_in"))
      (node (ref "U3") (pin "PAD") (pinfunction "GND_PAD") (pintype "power_in"))
      (node (ref "U4") (pin "1") (pinfunction "~{EN}_1") (pintype "bidirectional"))
      (node (ref "U4") (pin "10") (pinfunction "GND_10") (pintype "bidirectional"))
      (node (ref "U5") (pin "2") (pinfunction "GND_2") (pintype "power_in"))
      (node (ref "U6") (pin "P2") (pinfunction "GND_P2") (pintype "power_in"))
      (node (ref "U6") (pin "P8") (pinfunction "S_P8") (pintype "input"))
      (node (ref "U8") (pin "12") (pinfunction "GND_12") (pintype "power_in"))
      (node (ref "U8") (pin "2") (pinfunction "AD1_2") (pintype "bidirectional"))
      (node (ref "U8") (pin "21") (pinfunction "AD0_21") (pintype "bidirectional"))
      (node (ref "U8") (pin "3") (pinfunction "AD2_3") (pintype "bidirectional"))
    )
    (net (code "14") (name "I2C1_SCL") (class "Default")
      (node (ref "R24") (pin "2") (pinfunction "2_2") (pintype "passive"))
      (node (ref "U1") (pin "58") (pinfunction "PB6_58") (pintype "bidirectional"))
      (node (ref "U8") (pin "22") (pinfunction "SCL_22") (pintype "bidirectional"))
    )
    (net (code "15") (name "I2C1_SDA") (class "Default")
      (node (ref "R25") (pin "2") (pinfunction "2_2") (pintype "passive"))
      (node (ref "U1") (pin "59") (pinfunction "PB7_59") (pintype "bidirectional"))
      (node (ref "U8") (pin "23") (pinfunction "SDA_23") (pintype "bidirectional"))
    )
    (net (code "16") (name "LED_0") (class "Default")
      (node (ref "R4") (pin "1") (pinfunction "1_1") (pintype "passive"))
      (node (ref "U1") (pin "33") (pinfunction "PB12_33") (pintype "bidirectional"))
    )
    (net (code "17") (name "LED_1") (class "Default")
      (node (ref "R5") (pin "1") (pinfunction "1_1") (pintype "passive"))
      (node (ref "U1") (pin "34") (pinfunction "PB13_34") (pintype "bidirectional"))
    )
    (net (code "18") (name "LED_2") (class "Default")
      (node (ref "R6") (pin "1") (pinfunction "1_1") (pintype "passive"))
      (node (ref "U1") (pin "35") (pinfunction "PB14_35") (pintype "bidirectional"))
    )
    (net (code "19") (name "LED_3") (class "Default")
      (node (ref "R7") (pin "1") (pinfunction "1_1") (pintype "passive"))
      (node (ref "U1") (pin "36") (pinfunction "PB15_36") (pintype "bidirectional"))
    )
    (net (code "20") (name "LED_OIL") (class "Default")
      (node (ref "J1") (pin "2") (pinfunction "1_2") (pintype "passive"))
      (node (ref "R26") (pin "1") (pinfunction "1_1") (pintype "passive"))
    )
    (net (code "21") (name "LED_RPM0") (class "Default")
      (node (ref "J1") (pin "3") (pinfunction "1_3") (pintype "passive"))
      (node (ref "R27") (pin "1") (pinfunction "1_1") (pintype "passive"))
    )
    (net (code "22") (name "LED_RPM1") (class "Default")
      (node (ref "J1") (pin "4") (pinfunction "1_4") (pintype "passive"))
      (node (ref "R28") (pin "1") (pinfunction "1_1") (pintype "passive"))
    )
    (net (code "23") (name "LED_RPM2") (class "Default")
      (node (ref "J1") (pin "5") (pinfunction "1_5") (pintype "passive"))
      (node (ref "R29") (pin "1") (pinfunction "1_1") (pintype "passive"))
    )
    (net (code "24") (name "LED_RPM3") (class "Default")
      (node (ref "J1") (pin "6") (pinfunction "1_6") (pintype "passive"))
      (node (ref "R30") (pin "1") (pinfunction "1_1") (pintype "passive"))
    )
    (net (code "25") (name "LED_RPM4") (class "Default")
      (node (ref "J1") (pin "7") (pinfunction "1_7") (pintype "passive"))
      (node (ref "R31") (pin "1") (pinfunction "1_1") (pintype "passive"))
    )
    (net (code "26") (name "LED_RPM5") (class "Default")
      (node (ref "J1") (pin "8") (pinfunction "1_8") (pintype "passive"))
      (node (ref "R33") (pin "1") (pinfunction "1_1") (pintype "passive"))
    )
    (net (code "27") (name "LED_RPM6") (class "Default")
      (node (ref "J1") (pin "9") (pinfunction "1_9") (pintype "passive"))
      (node (ref "R32") (pin "1") (pinfunction "1_1") (pintype "passive"))
    )
    (net (code "28") (name "LED_RPM7") (class "Default")
      (node (ref "J1") (pin "10") (pinfunction "1_10") (pintype "passive"))
      (node (ref "R34") (pin "1") (pinfunction "1_1") (pintype "passive"))
    )
    (net (code "29") (name "LED_RPM8") (class "Default")
      (node (ref "J1") (pin "11") (pinfunction "1_11") (pintype "passive"))
      (node (ref "R35") (pin "1") (pinfunction "1_1") (pintype "passive"))
    )
    (net (code "30") (name "LED_RPM9") (class "Default")
      (node (ref "J1") (pin "12") (pinfunction "1_12") (pintype "passive"))
      (node (ref "R36") (pin "1") (pinfunction "1_1") (pintype "passive"))
    )
    (net (code "31") (name "LED_WATER") (class "Default")
      (node (ref "J1") (pin "13") (pinfunction "1_13") (pintype "passive"))
      (node (ref "R37") (pin "1") (pinfunction "1_1") (pintype "passive"))
    )
    (net (code "32") (name "MAX_ENTER") (class "Default")
      (node (ref "U1") (pin "28") (pinfunction "PB2_28") (pintype "bidirectional"))
      (node (ref "U4") (pin "15") (pinfunction "OUT5_15") (pintype "bidirectional"))
    )
    (net (code "33") (name "MAX_MINUS") (class "Default")
      (node (ref "U1") (pin "25") (pinfunction "PC5_25") (pintype "bidirectional"))
      (node (ref "U4") (pin "18") (pinfunction "OUT2_18") (pintype "bidirectional"))
    )
    (net (code "34") (name "MAX_PLUS") (class "Default")
      (node (ref "U1") (pin "27") (pinfunction "PB1_27") (pintype "bidirectional"))
      (node (ref "U4") (pin "16") (pinfunction "OUT4_16") (pintype "bidirectional"))
    )
    (net (code "35") (name "MAX_SHIFT_DOWN") (class "Default")
      (node (ref "U1") (pin "24") (pinfunction "PC4_24") (pintype "bidirectional"))
      (node (ref "U4") (pin "19") (pinfunction "OUT1_19") (pintype "bidirectional"))
    )
    (net (code "36") (name "MAX_SHIFT_UP") (class "Default")
      (node (ref "U1") (pin "26") (pinfunction "PB0_26") (pintype "bidirectional"))
      (node (ref "U4") (pin "17") (pinfunction "OUT3_17") (pintype "bidirectional"))
    )
    (net (code "37") (name "MINUS") (class "Default")
      (node (ref "J2") (pin "8") (pinfunction "1_8") (pintype "passive"))
      (node (ref "U4") (pin "3") (pinfunction "IN2_3") (pintype "bidirectional"))
    )
    (net (code "38") (name "Net-(DISPLAY-BAUD0(SS))") (class "Default")
      (node (ref "DISPLAY") (pin "P$6") (pinfunction "BAUD0(SS)_P$6") (pintype "bidirectional"))
      (node (ref "R16") (pin "2") (pinfunction "2_2") (pintype "passive"))
    )
    (net (code "39") (name "Net-(DISPLAY-BAUD1(MOSI))") (class "Default")
      (node (ref "DISPLAY") (pin "P$7") (pinfunction "BAUD1(MOSI)_P$7") (pintype "bidirectional"))
      (node (ref "R17") (pin "2") (pinfunction "2_2") (pintype "passive"))
    )
    (net (code "40") (name "Net-(DISPLAY-BAUD2(MISO))") (class "Default")
      (node (ref "DISPLAY") (pin "P$8") (pinfunction "BAUD2(MISO)_P$8") (pintype "bidirectional"))
      (node (ref "R18") (pin "2") (pinfunction "2_2") (pintype "passive"))
    )
    (net (code "41") (name "Net-(LED1-PadC)") (class "Default")
      (node (ref "LED1") (pin "C") (pinfunction "C_C") (pintype "passive"))
      (node (ref "R4") (pin "2") (pinfunction "2_2") (pintype "passive"))
    )
    (net (code "42") (name "Net-(LED2-PadC)") (class "Default")
      (node (ref "LED2") (pin "C") (pinfunction "C_C") (pintype "passive"))
      (node (ref "R5") (pin "2") (pinfunction "2_2") (pintype "passive"))
    )
    (net (code "43") (name "Net-(LED3-PadC)") (class "Default")
      (node (ref "LED3") (pin "C") (pinfunction "C_C") (pintype "passive"))
      (node (ref "R6") (pin "2") (pinfunction "2_2") (pintype "passive"))
    )
    (net (code "44") (name "Net-(LED4-PadC)") (class "Default")
      (node (ref "LED4") (pin "C") (pinfunction "C_C") (pintype "passive"))
      (node (ref "R7") (pin "2") (pinfunction "2_2") (pintype "passive"))
    )
    (net (code "45") (name "Net-(Q1-Q1)") (class "Default")
      (node (ref "C6") (pin "1") (pinfunction "1_1") (pintype "passive"))
      (node (ref "Q1") (pin "1") (pinfunction "Q1_1") (pintype "passive"))
      (node (ref "R2") (pin "2") (pinfunction "2_2") (pintype "passive"))
    )
    (net (code "46") (name "Net-(Q1-Q2)") (class "Default")
      (node (ref "C10") (pin "1") (pinfunction "1_1") (pintype "passive"))
      (node (ref "Q1") (pin "3") (pinfunction "Q2_3") (pintype "passive"))
      (node (ref "U1") (pin "5") (pinfunction "PH0/OSC_IN_5") (pintype "input"))
    )
    (net (code "47") (name "Net-(T1-G)") (class "Default")
      (node (ref "D1") (pin "A") (pinfunction "A_A") (pintype "passive"))
      (node (ref "R8") (pin "2") (pinfunction "2_2") (pintype "passive"))
      (node (ref "T1") (pin "3") (pinfunction "G_3") (pintype "passive"))
    )
    (net (code "48") (name "Net-(U1B-VCAP_1)") (class "Default")
      (node (ref "C12") (pin "1") (pinfunction "1_1") (pintype "passive"))
      (node (ref "U1") (pin "31") (pinfunction "VCAP_1_31") (pintype "power_in"))
    )
    (net (code "49") (name "Net-(U1B-VCAP_2)") (class "Default")
      (node (ref "C9") (pin "1") (pinfunction "1_1") (pintype "passive"))
      (node (ref "U1") (pin "47") (pinfunction "VCAP_2_47") (pintype "power_in"))
    )
    (net (code "50") (name "Net-(U1H-PH1{slash}OSC_OUT)") (class "Default")
      (node (ref "R2") (pin "1") (pinfunction "1_1") (pintype "passive"))
      (node (ref "U1") (pin "6") (pinfunction "PH1/OSC_OUT_6") (pintype "output"))
    )
    (net (code "51") (name "Net-(U1I-BOOT0)") (class "Default")
      (node (ref "R3") (pin "1") (pinfunction "1_1") (pintype "passive"))
      (node (ref "U1") (pin "60") (pinfunction "BOOT0_60") (pintype "input"))
    )
    (net (code "52") (name "Net-(U2-FB)") (class "Default")
      (node (ref "R12") (pin "1") (pinfunction "1_1") (pintype "passive"))
      (node (ref "R9") (pin "2") (pinfunction "2_2") (pintype "passive"))
      (node (ref "U2") (pin "2") (pinfunction "FB_2") (pintype "input"))
    )
    (net (code "53") (name "Net-(U2-PG)") (class "Default")
      (node (ref "R11") (pin "1") (pinfunction "1_1") (pintype "passive"))
      (node (ref "U2") (pin "3") (pinfunction "PG_3") (pintype "output"))
    )
    (net (code "54") (name "Net-(U2-SS)") (class "Default")
      (node (ref "C16") (pin "1") (pinfunction "1_1") (pintype "passive"))
      (node (ref "U2") (pin "1") (pinfunction "SS_1") (pintype "passive"))
    )
    (net (code "55") (name "Net-(U3-FB)") (class "Default")
      (node (ref "R10") (pin "2") (pinfunction "2_2") (pintype "passive"))
      (node (ref "R14") (pin "1") (pinfunction "1_1") (pintype "passive"))
      (node (ref "U3") (pin "2") (pinfunction "FB_2") (pintype "input"))
    )
    (net (code "56") (name "Net-(U3-PG)") (class "Default")
      (node (ref "R13") (pin "1") (pinfunction "1_1") (pintype "passive"))
      (node (ref "U3") (pin "3") (pinfunction "PG_3") (pintype "output"))
    )
    (net (code "57") (name "Net-(U3-SS)") (class "Default")
      (node (ref "C17") (pin "1") (pinfunction "1_1") (pintype "passive"))
      (node (ref "U3") (pin "1") (pinfunction "SS_1") (pintype "passive"))
    )
    (net (code "58") (name "Net-(U5-D1C)") (class "Default")
      (node (ref "K1") (pin "D+") (pinfunction "D+_D+") (pintype "passive"))
      (node (ref "U5") (pin "6") (pinfunction "D1C_6") (pintype "bidirectional"))
    )
    (net (code "59") (name "Net-(U5-D2C)") (class "Default")
      (node (ref "K1") (pin "D-") (pinfunction "D-_D-") (pintype "passive"))
      (node (ref "U5") (pin "4") (pinfunction "D2C_4") (pintype "bidirectional"))
    )
    (net (code "60") (name "Net-(U6-CANH)") (class "Default")
      (node (ref "L1") (pin "1") (pinfunction "1_1") (pintype "passive"))
      (node (ref "U6") (pin "P7") (pinfunction "CANH_P7") (pintype "bidirectional"))
    )
    (net (code "61") (name "Net-(U6-CANL)") (class "Default")
      (node (ref "L1") (pin "2") (pinfunction "2_2") (pintype "passive"))
      (node (ref "U6") (pin "P6") (pinfunction "CANL_P6") (pintype "bidirectional"))
    )
    (net (code "62") (name "Net-(U8-P0)") (class "Default")
      (node (ref "R26") (pin "2") (pinfunction "2_2") (pintype "passive"))
      (node (ref "U8") (pin "4") (pinfunction "P0_4") (pintype "passive"))
    )
    (net (code "63") (name "Net-(U8-P1)") (class "Default")
      (node (ref "R27") (pin "2") (pinfunction "2_2") (pintype "passive"))
      (node (ref "U8") (pin "5") (pinfunction "P1_5") (pintype "passive"))
    )
    (net (code "64") (name "Net-(U8-P2)") (class "Default")
      (node (ref "R28") (pin "2") (pinfunction "2_2") (pintype "passive"))
      (node (ref "U8") (pin "6") (pinfunction "P2_6") (pintype "passive"))
    )
    (net (code "65") (name "Net-(U8-P3)") (class "Default")
      (node (ref "R29") (pin "2") (pinfunction "2_2") (pintype "passive"))
      (node (ref "U8") (pin "7") (pinfunction "P3_7") (pintype "passive"))
    )
    (net (code "66") (name "Net-(U8-P4)") (class "Default")
      (node (ref "R30") (pin "2") (pinfunction "2_2") (pintype "passive"))
      (node (ref "U8") (pin "8") (pinfunction "P4_8") (pintype "passive"))
    )
    (net (code "67") (name "Net-(U8-P5)") (class "Default")
      (node (ref "R31") (pin "2") (pinfunction "2_2") (pintype "passive"))
      (node (ref "U8") (pin "9") (pinfunction "P5_9") (pintype "passive"))
    )
    (net (code "68") (name "Net-(U8-P6)") (class "Default")
      (node (ref "R33") (pin "2") (pinfunction "2_2") (pintype "passive"))
      (node (ref "U8") (pin "10") (pinfunction "P6_10") (pintype "passive"))
    )
    (net (code "69") (name "Net-(U8-P7)") (class "Default")
      (node (ref "R32") (pin "2") (pinfunction "2_2") (pintype "passive"))
      (node (ref "U8") (pin "11") (pinfunction "P7_11") (pintype "passive"))
    )
    (net (code "70") (name "Net-(U8-P8)") (class "Default")
      (node (ref "R34") (pin "2") (pinfunction "2_2") (pintype "passive"))
      (node (ref "U8") (pin "13") (pinfunction "P8_13") (pintype "passive"))
    )
    (net (code "71") (name "Net-(U8-P9)") (class "Default")
      (node (ref "R35") (pin "2") (pinfunction "2_2") (pintype "passive"))
      (node (ref "U8") (pin "14") (pinfunction "P9_14") (pintype "passive"))
    )
    (net (code "72") (name "Net-(U8-P10)") (class "Default")
      (node (ref "R36") (pin "2") (pinfunction "2_2") (pintype "passive"))
      (node (ref "U8") (pin "15") (pinfunction "P10_15") (pintype "passive"))
    )
    (net (code "73") (name "Net-(U8-P11)") (class "Default")
      (node (ref "R37") (pin "2") (pinfunction "2_2") (pintype "passive"))
      (node (ref "U8") (pin "16") (pinfunction "P11_16") (pintype "passive"))
    )
    (net (code "74") (name "PLUS") (class "Default")
      (node (ref "J2") (pin "11") (pinfunction "1_11") (pintype "passive"))
      (node (ref "U4") (pin "5") (pinfunction "IN4_5") (pintype "bidirectional"))
    )
    (net (code "75") (name "SHIFT_DOWN") (class "Default")
      (node (ref "J2") (pin "7") (pinfunction "1_7") (pintype "passive"))
      (node (ref "U4") (pin "2") (pinfunction "IN1_2") (pintype "bidirectional"))
    )
    (net (code "76") (name "SHIFT_UP") (class "Default")
      (node (ref "J2") (pin "10") (pinfunction "1_10") (pintype "passive"))
      (node (ref "U4") (pin "4") (pinfunction "IN3_4") (pintype "bidirectional"))
    )
    (net (code "77") (name "SWCLK") (class "Default")
      (node (ref "J3") (pin "4") (pinfunction "4_4") (pintype "passive"))
      (node (ref "R21") (pin "2") (pinfunction "2_2") (pintype "passive"))
      (node (ref "U1") (pin "49") (pinfunction "PA14_49") (pintype "bidirectional"))
    )
    (net (code "78") (name "SWDIO") (class "Default")
      (node (ref "J3") (pin "2") (pinfunction "2_2") (pintype "passive"))
      (node (ref "R22") (pin "2") (pinfunction "2_2") (pintype "passive"))
      (node (ref "U1") (pin "46") (pinfunction "PA13_46") (pintype "bidirectional"))
    )
    (net (code "79") (name "SWO") (class "Default")
      (node (ref "J3") (pin "6") (pinfunction "6_6") (pintype "passive"))
      (node (ref "R20") (pin "2") (pinfunction "2_2") (pintype "passive"))
      (node (ref "U1") (pin "55") (pinfunction "PB3_55") (pintype "bidirectional"))
    )
    (net (code "80") (name "UART4_RX") (class "Default")
      (node (ref "DISPLAY") (pin "P$11") (pinfunction "TXD(SPIMO)_P$11") (pintype "bidirectional"))
      (node (ref "U1") (pin "52") (pinfunction "PC11_52") (pintype "bidirectional"))
    )
    (net (code "81") (name "UART4_TX") (class "Default")
      (node (ref "DISPLAY") (pin "P$10") (pinfunction "RXD(DORD)_P$10") (pintype "bidirectional"))
      (node (ref "U1") (pin "51") (pinfunction "PC10_51") (pintype "bidirectional"))
    )
    (net (code "82") (name "USB_OTG_FS_DM") (class "Default")
      (node (ref "U1") (pin "44") (pinfunction "PA11_44") (pintype "bidirectional"))
      (node (ref "U5") (pin "3") (pinfunction "D2I_3") (pintype "bidirectional"))
    )
    (net (code "83") (name "USB_OTG_FS_DP") (class "Default")
      (node (ref "U1") (pin "45") (pinfunction "PA12_45") (pintype "bidirectional"))
      (node (ref "U5") (pin "1") (pinfunction "D1I_1") (pintype "bidirectional"))
    )
    (net (code "84") (name "USB_OTG_FS_ID") (class "Default")
      (node (ref "K1") (pin "ID") (pinfunction "ID_ID") (pintype "passive"))
      (node (ref "U1") (pin "43") (pinfunction "PA10_43") (pintype "bidirectional"))
    )
    (net (code "85") (name "USB_OTG_FS_VBUS") (class "Default")
      (node (ref "K1") (pin "VCC") (pinfunction "VCC_VCC") (pintype "passive"))
      (node (ref "U1") (pin "42") (pinfunction "PA9_42") (pintype "bidirectional"))
    )
    (net (code "86") (name "VCC") (class "Default")
      (node (ref "C14") (pin "1") (pinfunction "1_1") (pintype "passive"))
      (node (ref "C15") (pin "1") (pinfunction "1_1") (pintype "passive"))
      (node (ref "D1") (pin "C") (pinfunction "C_C") (pintype "passive"))
      (node (ref "D2") (pin "C") (pinfunction "2_C") (pintype "passive"))
      (node (ref "T1") (pin "4") (pinfunction "S_4") (pintype "passive"))
      (node (ref "U2") (pin "7") (pinfunction "EN_7") (pintype "input"))
      (node (ref "U2") (pin "8") (pinfunction "VIN_8") (pintype "power_in"))
      (node (ref "U3") (pin "8") (pinfunction "VIN_8") (pintype "power_in"))
    )
    (net (code "87") (name "V_IN") (class "Default")
      (node (ref "J2") (pin "1") (pinfunction "1_1") (pintype "passive"))
      (node (ref "T1") (pin "1") (pinfunction "D_1") (pintype "passive"))
      (node (ref "T1") (pin "2") (pinfunction "D_2") (pintype "passive"))
      (node (ref "T1") (pin "5") (pinfunction "D_5") (pintype "passive"))
      (node (ref "T1") (pin "6") (pinfunction "D_6") (pintype "passive"))
    )
    (net (code "88") (name "unconnected-(DISPLAY-ADR0(CLK)-PadP$9)") (class "Default")
      (node (ref "DISPLAY") (pin "P$9") (pinfunction "ADR0(CLK)_P$9") (pintype "bidirectional"))
    )
    (net (code "89") (name "unconnected-(DISPLAY-ADR1(CPOL)-PadP$14)") (class "Default")
      (node (ref "DISPLAY") (pin "P$14") (pinfunction "ADR1(CPOL)_P$14") (pintype "bidirectional"))
    )
    (net (code "90") (name "unconnected-(DISPLAY-ADR2(CPHA)-PadP$15)") (class "Default")
      (node (ref "DISPLAY") (pin "P$15") (pinfunction "ADR2(CPHA)_P$15") (pintype "bidirectional"))
    )
    (net (code "91") (name "unconnected-(DISPLAY-BUZZ-PadP$16)") (class "Default")
      (node (ref "DISPLAY") (pin "P$16") (pinfunction "BUZZ_P$16") (pintype "bidirectional"))
    )
    (net (code "92") (name "unconnected-(DISPLAY-DPOM-PadP$13)") (class "Default")
      (node (ref "DISPLAY") (pin "P$13") (pinfunction "DPOM_P$13") (pintype "bidirectional"))
    )
    (net (code "93") (name "unconnected-(DISPLAY-DPROT-PadP$17)") (class "Default")
      (node (ref "DISPLAY") (pin "P$17") (pinfunction "DPROT_P$17") (pintype "bidirectional"))
    )
    (net (code "94") (name "unconnected-(DISPLAY-EN485-PadP$12)") (class "Default")
      (node (ref "DISPLAY") (pin "P$12") (pinfunction "EN485_P$12") (pintype "bidirectional"))
    )
    (net (code "95") (name "unconnected-(J1G-1-Pad15)") (class "Default")
      (node (ref "J1") (pin "15") (pinfunction "1_15") (pintype "passive"))
    )
    (net (code "96") (name "unconnected-(J1H-1-Pad16)") (class "Default")
      (node (ref "J1") (pin "16") (pinfunction "1_16") (pintype "passive"))
    )
    (net (code "97") (name "unconnected-(J3-Pad7)") (class "Default")
      (node (ref "J3") (pin "7") (pinfunction "7_7") (pintype "passive"))
    )
    (net (code "98") (name "unconnected-(J3-Pad8)") (class "Default")
      (node (ref "J3") (pin "8") (pinfunction "8_8") (pintype "passive"))
    )
    (net (code "99") (name "unconnected-(J3-Pad9)") (class "Default")
      (node (ref "J3") (pin "9") (pinfunction "9_9") (pintype "passive"))
    )
    (net (code "100") (name "unconnected-(U1C-PA8-Pad41)") (class "Default")
      (node (ref "U1") (pin "41") (pinfunction "PA8_41") (pintype "bidirectional"))
    )
    (net (code "101") (name "unconnected-(U1D-PA0-Pad14)") (class "Default")
      (node (ref "U1") (pin "14") (pinfunction "PA0_14") (pintype "bidirectional"))
    )
    (net (code "102") (name "unconnected-(U1D-PA1-Pad15)") (class "Default")
      (node (ref "U1") (pin "15") (pinfunction "PA1_15") (pintype "bidirectional"))
    )
    (net (code "103") (name "unconnected-(U1D-PA2-Pad16)") (class "Default")
      (node (ref "U1") (pin "16") (pinfunction "PA2_16") (pintype "bidirectional"))
    )
    (net (code "104") (name "unconnected-(U1D-PA5-Pad21)") (class "Default")
      (node (ref "U1") (pin "21") (pinfunction "PA5_21") (pintype "bidirectional"))
    )
    (net (code "105") (name "unconnected-(U1D-PA6-Pad22)") (class "Default")
      (node (ref "U1") (pin "22") (pinfunction "PA6_22") (pintype "bidirectional"))
    )
    (net (code "106") (name "unconnected-(U1D-PA7-Pad23)") (class "Default")
      (node (ref "U1") (pin "23") (pinfunction "PA7_23") (pintype "bidirectional"))
    )
    (net (code "107") (name "unconnected-(U1E-PB11-Pad30)") (class "Default")
      (node (ref "U1") (pin "30") (pinfunction "PB11_30") (pintype "bidirectional"))
    )
    (net (code "108") (name "unconnected-(U1F-PB5-Pad57)") (class "Default")
      (node (ref "U1") (pin "57") (pinfunction "PB5_57") (pintype "bidirectional"))
    )
    (net (code "109") (name "unconnected-(U1J-PC8-Pad39)") (class "Default")
      (node (ref "U1") (pin "39") (pinfunction "PC8_39") (pintype "bidirectional"))
    )
    (net (code "110") (name "unconnected-(U1J-PC9-Pad40)") (class "Default")
      (node (ref "U1") (pin "40") (pinfunction "PC9_40") (pintype "bidirectional"))
    )
    (net (code "111") (name "unconnected-(U1J-PC12-Pad53)") (class "Default")
      (node (ref "U1") (pin "53") (pinfunction "PC12_53") (pintype "bidirectional"))
    )
    (net (code "112") (name "unconnected-(U1J-PC13-Pad2)") (class "Default")
      (node (ref "U1") (pin "2") (pinfunction "PC13_2") (pintype "bidirectional"))
    )
    (net (code "113") (name "unconnected-(U1J-PC14{slash}OSC32_IN-Pad3)") (class "Default")
      (node (ref "U1") (pin "3") (pinfunction "PC14/OSC32_IN_3") (pintype "bidirectional"))
    )
    (net (code "114") (name "unconnected-(U1J-PC15{slash}OSC32_OUT-Pad4)") (class "Default")
      (node (ref "U1") (pin "4") (pinfunction "PC15/OSC32_OUT_4") (pintype "bidirectional"))
    )
    (net (code "115") (name "unconnected-(U1K-PC1-Pad9)") (class "Default")
      (node (ref "U1") (pin "9") (pinfunction "PC1_9") (pintype "bidirectional"))
    )
    (net (code "116") (name "unconnected-(U1K-PC2-Pad10)") (class "Default")
      (node (ref "U1") (pin "10") (pinfunction "PC2_10") (pintype "bidirectional"))
    )
    (net (code "117") (name "unconnected-(U1K-PC3-Pad11)") (class "Default")
      (node (ref "U1") (pin "11") (pinfunction "PC3_11") (pintype "bidirectional"))
    )
    (net (code "118") (name "unconnected-(U1K-PC6-Pad37)") (class "Default")
      (node (ref "U1") (pin "37") (pinfunction "PC6_37") (pintype "bidirectional"))
    )
    (net (code "119") (name "unconnected-(U1K-PC7-Pad38)") (class "Default")
      (node (ref "U1") (pin "38") (pinfunction "PC7_38") (pintype "bidirectional"))
    )
    (net (code "120") (name "unconnected-(U4-IN6-Pad7)") (class "Default")
      (node (ref "U4") (pin "7") (pinfunction "IN6_7") (pintype "bidirectional"))
    )
    (net (code "121") (name "unconnected-(U4-IN7-Pad8)") (class "Default")
      (node (ref "U4") (pin "8") (pinfunction "IN7_8") (pintype "bidirectional"))
    )
    (net (code "122") (name "unconnected-(U4-IN8-Pad9)") (class "Default")
      (node (ref "U4") (pin "9") (pinfunction "IN8_9") (pintype "bidirectional"))
    )
    (net (code "123") (name "unconnected-(U4-OUT6-Pad14)") (class "Default")
      (node (ref "U4") (pin "14") (pinfunction "OUT6_14") (pintype "bidirectional"))
    )
    (net (code "124") (name "unconnected-(U4-OUT7-Pad13)") (class "Default")
      (node (ref "U4") (pin "13") (pinfunction "OUT7_13") (pintype "bidirectional"))
    )
    (net (code "125") (name "unconnected-(U4-OUT8-Pad12)") (class "Default")
      (node (ref "U4") (pin "12") (pinfunction "OUT8_12") (pintype "bidirectional"))
    )
    (net (code "126") (name "unconnected-(U8-P12-Pad17)") (class "Default")
      (node (ref "U8") (pin "17") (pinfunction "P12_17") (pintype "passive"))
    )
    (net (code "127") (name "unconnected-(U8-P13-Pad18)") (class "Default")
      (node (ref "U8") (pin "18") (pinfunction "P13_18") (pintype "passive"))
    )
    (net (code "128") (name "unconnected-(U8-P14-Pad19)") (class "Default")
      (node (ref "U8") (pin "19") (pinfunction "P14_19") (pintype "passive"))
    )
    (net (code "129") (name "unconnected-(U8-P15-Pad20)") (class "Default")
      (node (ref "U8") (pin "20") (pinfunction "P15_20") (pintype "passive"))
    )
    (net (code "130") (name "unconnected-(U8-~{INT}-Pad1)") (class "Default")
      (node (ref "U8") (pin "1") (pinfunction "~{INT}_1") (pintype "bidirectional"))
    )
    (net (code "131") (name "~{MAX_CH}") (class "Default")
      (node (ref "R23") (pin "1") (pinfunction "1_1") (pintype "passive"))
      (node (ref "U1") (pin "29") (pinfunction "PB10_29") (pintype "bidirectional"))
      (node (ref "U4") (pin "11") (pinfunction "~{CH}_11") (pintype "bidirectional"))
    )
    (net (code "132") (name "~{RESET}") (class "Default")
      (node (ref "C13") (pin "1") (pinfunction "1_1") (pintype "passive"))
      (node (ref "J3") (pin "10") (pinfunction "10_10") (pintype "passive"))
      (node (ref "R1") (pin "2") (pinfunction "2_2") (pintype "passive"))
      (node (ref "U1") (pin "7") (pinfunction "NRST_7") (pintype "input"))
    )
  )
)
